# openvfo_nextion_teensy_4_0.net
KiCad netlist of a schematic drawn in EAGLE
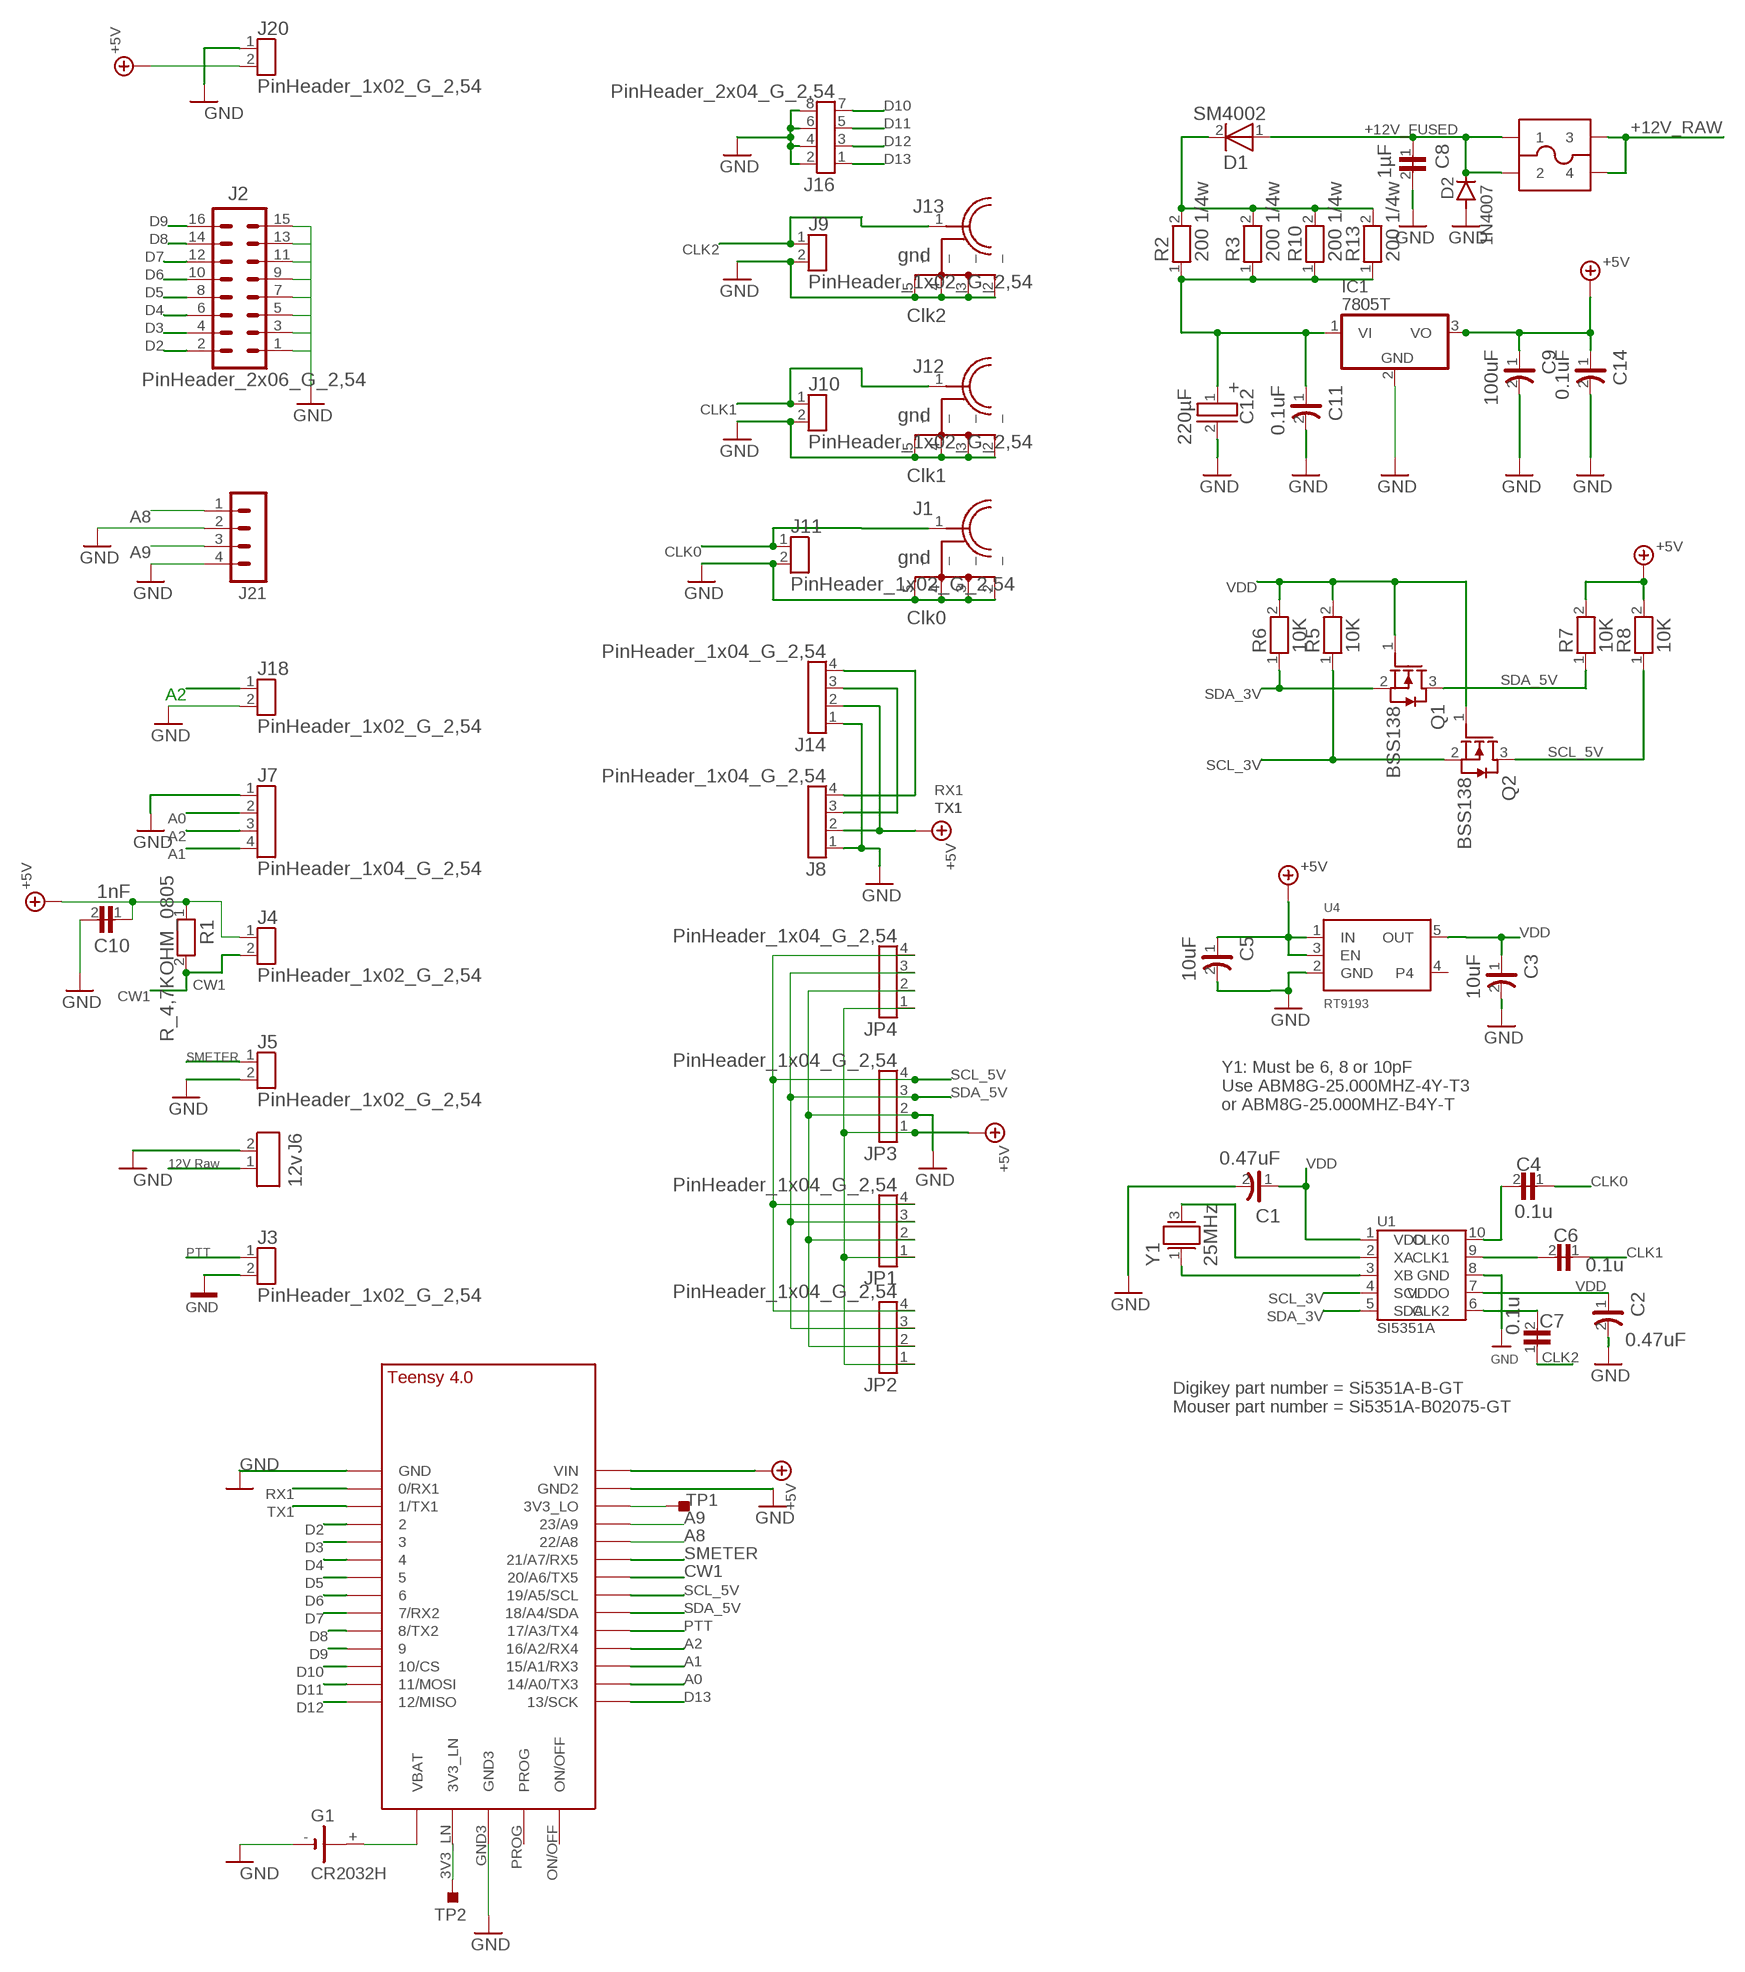
[diagram p0: schematic, sheet 1]

(export (version "E")
  (design (tool "Eeschema 10.0.6"))
  (components
    (comp (ref "C1")
      (value "0.47uF")
      (footprint "eagle-import:0805_3")
      (libsource (lib "eagle-import") (part "C-0805_3"))
    )
    (comp (ref "C2")
      (value "0.47uF")
      (footprint "eagle-import:0805_4")
      (libsource (lib "eagle-import") (part "C-0805_4"))
    )
    (comp (ref "C3")
      (value "10uF")
      (footprint "eagle-import:0805_13")
      (libsource (lib "eagle-import") (part "C-0805_13"))
    )
    (comp (ref "C4")
      (value "0.1u")
      (footprint "eagle-import:0805_81")
      (libsource (lib "eagle-import") (part "C_0805_1000PF_50V__81"))
    )
    (comp (ref "C5")
      (value "10uF")
      (footprint "eagle-import:0805_12")
      (libsource (lib "eagle-import") (part "C-0805_12"))
    )
    (comp (ref "C6")
      (value "0.1u")
      (footprint "eagle-import:0805_82")
      (libsource (lib "eagle-import") (part "C_0805_1000PF_50V__82"))
    )
    (comp (ref "C7")
      (value "0.1u")
      (footprint "eagle-import:0805_83")
      (libsource (lib "eagle-import") (part "C_0805_1000PF_50V__83"))
    )
    (comp (ref "C8")
      (value "1µF")
      (footprint "eagle-import:1206_84")
      (libsource (lib "eagle-import") (part "CMCC_1206_1,0µF_50V_10%_X7R_84"))
    )
    (comp (ref "C9")
      (value "100uF")
      (footprint "eagle-import:0805_95")
      (libsource (lib "eagle-import") (part "C-0805_95"))
    )
    (comp (ref "C10")
      (value "1nF")
      (footprint "eagle-import:0805_23")
      (libsource (lib "eagle-import") (part "C_0805_1000PF_50V__23"))
    )
    (comp (ref "C11")
      (value "0.1uF")
      (footprint "eagle-import:0805_89")
      (libsource (lib "eagle-import") (part "C-0805_89"))
    )
    (comp (ref "C12")
      (value "220µF")
      (footprint "eagle-import:D8R3,81_ELKO_104")
      (libsource (lib "eagle-import") (part "RE2J_25V_220µF_104"))
    )
    (comp (ref "C14")
      (value "0.1uF")
      (footprint "eagle-import:0805_96")
      (libsource (lib "eagle-import") (part "C-0805_96"))
    )
    (comp (ref "D1")
      (value "SM4002")
      (footprint "eagle-import:MELF_85")
      (libsource (lib "eagle-import") (part "SM4002_85"))
    )
    (comp (ref "D2")
      (value "1N4007")
      (footprint "eagle-import:DO41-10")
      (libsource (lib "eagle-import") (part "1N4004"))
    )
    (comp (ref "F1")
      (value "SMALLFUSE")
      (footprint "eagle-import:SMALLFUSE")
      (fields (field (name "MFG") "Keystone") (field (name "MPN") "3568"))
      (libsource (lib "eagle-import") (part "SMALLFUSE"))
    )
    (comp (ref "G1")
      (value "CR2032H")
      (footprint "eagle-import:CR2032H")
      (libsource (lib "eagle-import") (part "CR2032H"))
    )
    (comp (ref "IC1")
      (value "7805T")
      (footprint "eagle-import:TO220H")
      (libsource (lib "eagle-import") (part "78T05"))
    )
    (comp (ref "J1")
      (value "Clk0")
      (footprint "eagle-import:SMA-EINBAUBUCHSE_67")
      (libsource (lib "eagle-import") (part "SMA-EINBAUBUCHSE_67"))
    )
    (comp (ref "J2")
      (value "PinHeader_2x06_G_2,54")
      (footprint "eagle-import:MA08-2")
      (libsource (lib "eagle-import") (part "MA08-2"))
    )
    (comp (ref "J3")
      (value "PinHeader_1x02_G_2,54")
      (footprint "eagle-import:STIFTLEISTE_1X02_G_2,54_17")
      (libsource (lib "eagle-import") (part "PINHEADER_1X02_G_2,54_17"))
    )
    (comp (ref "J4")
      (value "PinHeader_1x02_G_2,54")
      (footprint "eagle-import:STIFTLEISTE_1X02_G_2,54_18")
      (libsource (lib "eagle-import") (part "PINHEADER_1X02_G_2,54_18"))
    )
    (comp (ref "J5")
      (value "PinHeader_1x02_G_2,54")
      (footprint "eagle-import:STIFTLEISTE_1X02_G_2,54_19")
      (libsource (lib "eagle-import") (part "PINHEADER_1X02_G_2,54_19"))
    )
    (comp (ref "J6")
      (value "12v")
      (footprint "eagle-import:SL-MTA_2.54_2POL_20")
      (libsource (lib "eagle-import") (part "640456-2_20"))
    )
    (comp (ref "J7")
      (value "PinHeader_1x04_G_2,54")
      (footprint "eagle-import:STIFTLEISTE_1X04_G_2,54_15")
      (libsource (lib "eagle-import") (part "PINHEADER_1X04_G_2,54_15"))
    )
    (comp (ref "J8")
      (value "PinHeader_1x04_G_2,54")
      (footprint "eagle-import:STIFTLEISTE_1X04_G_2,54_22")
      (libsource (lib "eagle-import") (part "PINHEADER_1X04_G_2,54_22"))
    )
    (comp (ref "J9")
      (value "PinHeader_1x02_G_2,54")
      (footprint "eagle-import:STIFTLEISTE_1X02_G_2,54_49")
      (libsource (lib "eagle-import") (part "PINHEADER_1X02_G_2,54_49"))
    )
    (comp (ref "J10")
      (value "PinHeader_1x02_G_2,54")
      (footprint "eagle-import:STIFTLEISTE_1X02_G_2,54_50")
      (libsource (lib "eagle-import") (part "PINHEADER_1X02_G_2,54_50"))
    )
    (comp (ref "J11")
      (value "PinHeader_1x02_G_2,54")
      (footprint "eagle-import:STIFTLEISTE_1X02_G_2,54_51")
      (libsource (lib "eagle-import") (part "PINHEADER_1X02_G_2,54_51"))
    )
    (comp (ref "J12")
      (value "Clk1")
      (footprint "eagle-import:SMA-EINBAUBUCHSE_68")
      (libsource (lib "eagle-import") (part "SMA-EINBAUBUCHSE_68"))
    )
    (comp (ref "J13")
      (value "Clk2")
      (footprint "eagle-import:SMA-EINBAUBUCHSE_69")
      (libsource (lib "eagle-import") (part "SMA-EINBAUBUCHSE_69"))
    )
    (comp (ref "J14")
      (value "PinHeader_1x04_G_2,54")
      (footprint "eagle-import:STIFTLEISTE_1X04_G_2,54_70")
      (libsource (lib "eagle-import") (part "PINHEADER_1X04_G_2,54_70"))
    )
    (comp (ref "J16")
      (value "PinHeader_2x04_G_2,54")
      (footprint "eagle-import:STIFTLEISTE_2X04_G_2,54_71")
      (libsource (lib "eagle-import") (part "PINHEADER_2X04_G_2,54_71"))
    )
    (comp (ref "J18")
      (value "PinHeader_1x02_G_2,54")
      (footprint "eagle-import:STIFTLEISTE_1X02_G_2,54_97")
      (libsource (lib "eagle-import") (part "PINHEADER_1X02_G_2,54_97"))
    )
    (comp (ref "J20")
      (value "PinHeader_1x02_G_2,54")
      (footprint "eagle-import:STIFTLEISTE_1X02_G_2,54_137")
      (libsource (lib "eagle-import") (part "PINHEADER_1X02_G_2,54_137"))
    )
    (comp (ref "J21")
      (value "MA04-1")
      (footprint "eagle-import:MA04-1")
      (libsource (lib "eagle-import") (part "MA04-1"))
    )
    (comp (ref "JP1")
      (value "PinHeader_1x04_G_2,54")
      (footprint "eagle-import:STIFTLEISTE_1X04_G_2,54_14")
      (libsource (lib "eagle-import") (part "PINHEADER_1X04_G_2,54_14"))
    )
    (comp (ref "JP2")
      (value "PinHeader_1x04_G_2,54")
      (footprint "eagle-import:STIFTLEISTE_1X04_G_2,54_14")
      (libsource (lib "eagle-import") (part "PINHEADER_1X04_G_2,54_14"))
    )
    (comp (ref "JP3")
      (value "PinHeader_1x04_G_2,54")
      (footprint "eagle-import:STIFTLEISTE_1X04_G_2,54_14")
      (libsource (lib "eagle-import") (part "PINHEADER_1X04_G_2,54_14"))
    )
    (comp (ref "JP4")
      (value "PinHeader_1x04_G_2,54")
      (footprint "eagle-import:STIFTLEISTE_1X04_G_2,54_14")
      (libsource (lib "eagle-import") (part "PINHEADER_1X04_G_2,54_14"))
    )
    (comp (ref "Q1")
      (value "BSS138")
      (footprint "eagle-import:SOT23_3_7")
      (libsource (lib "eagle-import") (part "BSS138_7"))
    )
    (comp (ref "Q2")
      (value "BSS138")
      (footprint "eagle-import:SOT23_3_8")
      (libsource (lib "eagle-import") (part "BSS138_8"))
    )
    (comp (ref "R1")
      (value "R_4,7KOHM_0805")
      (footprint "eagle-import:0805_21")
      (libsource (lib "eagle-import") (part "R_4,7KOHM_0805_21"))
    )
    (comp (ref "R2")
      (value "200 1/4w")
      (footprint "eagle-import:0805_142")
      (libsource (lib "eagle-import") (part "R_SMD_200-OHM_0805_142"))
    )
    (comp (ref "R3")
      (value "200 1/4w")
      (footprint "eagle-import:0805_145")
      (libsource (lib "eagle-import") (part "R_SMD_200-OHM_0805_145"))
    )
    (comp (ref "R5")
      (value "10K")
      (footprint "eagle-import:0805_5")
      (libsource (lib "eagle-import") (part "R_SMD_10K_0805_5"))
    )
    (comp (ref "R6")
      (value "10K")
      (footprint "eagle-import:0805_6")
      (libsource (lib "eagle-import") (part "R_SMD_10K_0805_6"))
    )
    (comp (ref "R7")
      (value "10K")
      (footprint "eagle-import:0805_9")
      (libsource (lib "eagle-import") (part "R_SMD_10K_0805_9"))
    )
    (comp (ref "R8")
      (value "10K")
      (footprint "eagle-import:0805_10")
      (libsource (lib "eagle-import") (part "R_SMD_10K_0805_10"))
    )
    (comp (ref "R10")
      (value "200 1/4w")
      (footprint "eagle-import:0805_146")
      (libsource (lib "eagle-import") (part "R_SMD_200-OHM_0805_146"))
    )
    (comp (ref "R13")
      (value "200 1/4w")
      (footprint "eagle-import:0805_147")
      (libsource (lib "eagle-import") (part "R_SMD_200-OHM_0805_147"))
    )
    (comp (ref "TP1")
      (value "TESTPOINT_TPS-PAD-036")
      (footprint "eagle-import:TESTPOINT_PAD-036")
      (libsource (lib "eagle-import") (part "TESTPOINT_TPS-PAD-036"))
    )
    (comp (ref "TP2")
      (value "TESTPOINT_TPS-PAD-036")
      (footprint "eagle-import:TESTPOINT_PAD-036")
      (libsource (lib "eagle-import") (part "TESTPOINT_TPS-PAD-036"))
    )
    (comp (ref "U$1")
      (value "TEENSY_4.0")
      (footprint "eagle-import:TEENSY_4.0")
      (libsource (lib "eagle-import") (part "TEENSY_4.0"))
    )
    (comp (ref "U1")
      (value "SI5351A")
      (footprint "eagle-import:MSOP10_WB3X3_P0,5_0")
      (libsource (lib "eagle-import") (part "SI5351A_0"))
    )
    (comp (ref "U4")
      (value "RT9193")
      (footprint "eagle-import:SOT23-5_11")
      (libsource (lib "eagle-import") (part "VREG_SOT23-5_11"))
    )
    (comp (ref "Y1")
      (value "25MHz")
      (footprint "eagle-import:CFPX-104_1")
      (libsource (lib "eagle-import") (part "LFXTAL033075_1"))
    )
  )
  (nets
    (net (code "1") (name "+5V") (class "Default")
      (node (ref "C10") (pin "1") (pinfunction "1_1") (pintype "passive"))
      (node (ref "C14") (pin "1") (pinfunction "1_1") (pintype "passive"))
      (node (ref "C5") (pin "1") (pinfunction "1_1") (pintype "passive"))
      (node (ref "C9") (pin "1") (pinfunction "1_1") (pintype "passive"))
      (node (ref "IC1") (pin "3") (pinfunction "VO_3") (pintype "passive"))
      (node (ref "J14") (pin "2") (pinfunction "2_2") (pintype "passive"))
      (node (ref "J20") (pin "2") (pinfunction "2_2") (pintype "passive"))
      (node (ref "J4") (pin "1") (pinfunction "1_1") (pintype "passive"))
      (node (ref "J8") (pin "2") (pinfunction "2_2") (pintype "passive"))
      (node (ref "JP1") (pin "1") (pinfunction "1_1") (pintype "passive"))
      (node (ref "JP2") (pin "1") (pinfunction "1_1") (pintype "passive"))
      (node (ref "JP3") (pin "1") (pinfunction "1_1") (pintype "passive"))
      (node (ref "JP4") (pin "1") (pinfunction "1_1") (pintype "passive"))
      (node (ref "R1") (pin "1") (pinfunction "1_1") (pintype "passive"))
      (node (ref "R7") (pin "2") (pinfunction "2_2") (pintype "passive"))
      (node (ref "R8") (pin "2") (pinfunction "2_2") (pintype "passive"))
      (node (ref "U$1") (pin "VIN") (pinfunction "VIN_VIN") (pintype "bidirectional"))
      (node (ref "U4") (pin "1") (pinfunction "IN_1") (pintype "power_in"))
      (node (ref "U4") (pin "3") (pinfunction "EN_3") (pintype "input"))
    )
    (net (code "2") (name "/+12V_FUSED") (class "Default")
      (node (ref "C8") (pin "1") (pinfunction "1_1") (pintype "passive"))
      (node (ref "D1") (pin "1") (pinfunction "1_1") (pintype "passive"))
      (node (ref "D2") (pin "C") (pinfunction "C_C") (pintype "passive"))
      (node (ref "F1") (pin "P$1") (pinfunction "1_P$1") (pintype "bidirectional"))
      (node (ref "F1") (pin "P$2") (pinfunction "2_P$2") (pintype "bidirectional"))
    )
    (net (code "3") (name "/+12V_RAW") (class "Default")
      (node (ref "F1") (pin "P$3") (pinfunction "3_P$3") (pintype "bidirectional"))
      (node (ref "F1") (pin "P$4") (pinfunction "4_P$4") (pintype "bidirectional"))
      (node (ref "J6") (pin "1") (pinfunction "1_1") (pintype "passive"))
    )
    (net (code "4") (name "/A0") (class "Default")
      (node (ref "J7") (pin "2") (pinfunction "2_2") (pintype "passive"))
      (node (ref "U$1") (pin "14/A0") (pinfunction "14/A0/TX3_14/A0") (pintype "bidirectional"))
    )
    (net (code "5") (name "/A1") (class "Default")
      (node (ref "J7") (pin "4") (pinfunction "4_4") (pintype "passive"))
      (node (ref "U$1") (pin "15/A1") (pinfunction "15/A1/RX3_15/A1") (pintype "bidirectional"))
    )
    (net (code "6") (name "/A2") (class "Default")
      (node (ref "J18") (pin "1") (pinfunction "1_1") (pintype "passive"))
      (node (ref "J7") (pin "3") (pinfunction "3_3") (pintype "passive"))
      (node (ref "U$1") (pin "16/A2") (pinfunction "16/A2/RX4_16/A2") (pintype "bidirectional"))
    )
    (net (code "7") (name "/A8") (class "Default")
      (node (ref "J21") (pin "1") (pinfunction "1_1") (pintype "passive"))
      (node (ref "U$1") (pin "22/A8") (pinfunction "22/A8_22/A8") (pintype "bidirectional"))
    )
    (net (code "8") (name "/A9") (class "Default")
      (node (ref "J21") (pin "3") (pinfunction "3_3") (pintype "passive"))
      (node (ref "U$1") (pin "23/A9") (pinfunction "23/A9_23/A9") (pintype "bidirectional"))
    )
    (net (code "9") (name "/CLK0") (class "Default")
      (node (ref "C4") (pin "1") (pinfunction "1_1") (pintype "passive"))
      (node (ref "J1") (pin "1") (pinfunction "1_1") (pintype "passive"))
      (node (ref "J11") (pin "1") (pinfunction "1_1") (pintype "passive"))
    )
    (net (code "10") (name "/CLK1") (class "Default")
      (node (ref "C6") (pin "1") (pinfunction "1_1") (pintype "passive"))
      (node (ref "J10") (pin "1") (pinfunction "1_1") (pintype "passive"))
      (node (ref "J12") (pin "1") (pinfunction "1_1") (pintype "passive"))
    )
    (net (code "11") (name "/CLK2") (class "Default")
      (node (ref "C7") (pin "1") (pinfunction "1_1") (pintype "passive"))
      (node (ref "J13") (pin "1") (pinfunction "1_1") (pintype "passive"))
      (node (ref "J9") (pin "1") (pinfunction "1_1") (pintype "passive"))
    )
    (net (code "12") (name "/CW1") (class "Default")
      (node (ref "J4") (pin "2") (pinfunction "2_2") (pintype "passive"))
      (node (ref "R1") (pin "2") (pinfunction "2_2") (pintype "passive"))
      (node (ref "U$1") (pin "20/A6") (pinfunction "20/A6/TX5_20/A6") (pintype "bidirectional"))
    )
    (net (code "13") (name "/D2") (class "Default")
      (node (ref "J2") (pin "2") (pinfunction "2_2") (pintype "passive"))
      (node (ref "U$1") (pin "2") (pinfunction "2_2") (pintype "bidirectional"))
    )
    (net (code "14") (name "/D3") (class "Default")
      (node (ref "J2") (pin "4") (pinfunction "4_4") (pintype "passive"))
      (node (ref "U$1") (pin "3/CANTX") (pinfunction "3_3/CANTX") (pintype "bidirectional"))
    )
    (net (code "15") (name "/D4") (class "Default")
      (node (ref "J2") (pin "6") (pinfunction "6_6") (pintype "passive"))
      (node (ref "U$1") (pin "4/CANRX") (pinfunction "4_4/CANRX") (pintype "bidirectional"))
    )
    (net (code "16") (name "/D5") (class "Default")
      (node (ref "J2") (pin "8") (pinfunction "8_8") (pintype "passive"))
      (node (ref "U$1") (pin "5") (pinfunction "5_5") (pintype "bidirectional"))
    )
    (net (code "17") (name "/D6") (class "Default")
      (node (ref "J2") (pin "10") (pinfunction "10_10") (pintype "passive"))
      (node (ref "U$1") (pin "6") (pinfunction "6_6") (pintype "bidirectional"))
    )
    (net (code "18") (name "/D7") (class "Default")
      (node (ref "J2") (pin "12") (pinfunction "12_12") (pintype "passive"))
      (node (ref "U$1") (pin "7") (pinfunction "7/RX2_7") (pintype "bidirectional"))
    )
    (net (code "19") (name "/D8") (class "Default")
      (node (ref "J2") (pin "14") (pinfunction "14_14") (pintype "passive"))
      (node (ref "U$1") (pin "8") (pinfunction "8/TX2_8") (pintype "bidirectional"))
    )
    (net (code "20") (name "/D9") (class "Default")
      (node (ref "J2") (pin "16") (pinfunction "16_16") (pintype "passive"))
      (node (ref "U$1") (pin "9/CS") (pinfunction "9_9/CS") (pintype "bidirectional"))
    )
    (net (code "21") (name "/D10") (class "Default")
      (node (ref "J16") (pin "7") (pinfunction "7_7") (pintype "passive"))
      (node (ref "U$1") (pin "10/CS") (pinfunction "10/CS_10/CS") (pintype "bidirectional"))
    )
    (net (code "22") (name "/D11") (class "Default")
      (node (ref "J16") (pin "5") (pinfunction "5_5") (pintype "passive"))
      (node (ref "U$1") (pin "11/MOSI") (pinfunction "11/MOSI_11/MOSI") (pintype "bidirectional"))
    )
    (net (code "23") (name "/D12") (class "Default")
      (node (ref "J16") (pin "3") (pinfunction "3_3") (pintype "passive"))
      (node (ref "U$1") (pin "12/MISO") (pinfunction "12/MISO_12/MISO") (pintype "bidirectional"))
    )
    (net (code "24") (name "/D13") (class "Default")
      (node (ref "J16") (pin "1") (pinfunction "1_1") (pintype "passive"))
      (node (ref "U$1") (pin "13/SCK") (pinfunction "13/SCK_13/SCK") (pintype "bidirectional"))
    )
    (net (code "25") (name "/PTT") (class "Default")
      (node (ref "J3") (pin "1") (pinfunction "1_1") (pintype "passive"))
      (node (ref "U$1") (pin "17/A3") (pinfunction "17/A3/TX4_17/A3") (pintype "bidirectional"))
    )
    (net (code "26") (name "/RX1") (class "Default")
      (node (ref "J14") (pin "4") (pinfunction "4_4") (pintype "passive"))
      (node (ref "J8") (pin "4") (pinfunction "4_4") (pintype "passive"))
      (node (ref "U$1") (pin "0/RX") (pinfunction "0/RX1_0/RX") (pintype "bidirectional"))
    )
    (net (code "27") (name "/SCL_3V") (class "Default")
      (node (ref "Q2") (pin "2") (pinfunction "2_2") (pintype "passive"))
      (node (ref "R5") (pin "1") (pinfunction "1_1") (pintype "passive"))
      (node (ref "U1") (pin "4") (pinfunction "SCL_4") (pintype "passive"))
    )
    (net (code "28") (name "/SCL_5V") (class "Default")
      (node (ref "JP1") (pin "4") (pinfunction "4_4") (pintype "passive"))
      (node (ref "JP2") (pin "4") (pinfunction "4_4") (pintype "passive"))
      (node (ref "JP3") (pin "4") (pinfunction "4_4") (pintype "passive"))
      (node (ref "JP4") (pin "4") (pinfunction "4_4") (pintype "passive"))
      (node (ref "Q2") (pin "3") (pinfunction "3_3") (pintype "passive"))
      (node (ref "R8") (pin "1") (pinfunction "1_1") (pintype "passive"))
      (node (ref "U$1") (pin "19/A5/SCL") (pinfunction "19/A5/SCL_19/A5/SCL") (pintype "bidirectional"))
    )
    (net (code "29") (name "/SDA_3V") (class "Default")
      (node (ref "Q1") (pin "2") (pinfunction "2_2") (pintype "passive"))
      (node (ref "R6") (pin "1") (pinfunction "1_1") (pintype "passive"))
      (node (ref "U1") (pin "5") (pinfunction "SDA_5") (pintype "passive"))
    )
    (net (code "30") (name "/SDA_5V") (class "Default")
      (node (ref "JP1") (pin "3") (pinfunction "3_3") (pintype "passive"))
      (node (ref "JP2") (pin "3") (pinfunction "3_3") (pintype "passive"))
      (node (ref "JP3") (pin "3") (pinfunction "3_3") (pintype "passive"))
      (node (ref "JP4") (pin "3") (pinfunction "3_3") (pintype "passive"))
      (node (ref "Q1") (pin "3") (pinfunction "3_3") (pintype "passive"))
      (node (ref "R7") (pin "1") (pinfunction "1_1") (pintype "passive"))
      (node (ref "U$1") (pin "18/A4/SDA") (pinfunction "18/A4/SDA_18/A4/SDA") (pintype "bidirectional"))
    )
    (net (code "31") (name "/SMETER") (class "Default")
      (node (ref "J5") (pin "1") (pinfunction "1_1") (pintype "passive"))
      (node (ref "U$1") (pin "21/A7") (pinfunction "21/A7/RX5_21/A7") (pintype "bidirectional"))
    )
    (net (code "32") (name "/TX1") (class "Default")
      (node (ref "J14") (pin "3") (pinfunction "3_3") (pintype "passive"))
      (node (ref "J8") (pin "3") (pinfunction "3_3") (pintype "passive"))
      (node (ref "U$1") (pin "1/TX") (pinfunction "1/TX1_1/TX") (pintype "bidirectional"))
    )
    (net (code "33") (name "/VDD") (class "Default")
      (node (ref "C1") (pin "1") (pinfunction "1_1") (pintype "passive"))
      (node (ref "C2") (pin "1") (pinfunction "1_1") (pintype "passive"))
      (node (ref "C3") (pin "1") (pinfunction "1_1") (pintype "passive"))
      (node (ref "Q1") (pin "1") (pinfunction "1_1") (pintype "passive"))
      (node (ref "Q2") (pin "1") (pinfunction "1_1") (pintype "passive"))
      (node (ref "R5") (pin "2") (pinfunction "2_2") (pintype "passive"))
      (node (ref "R6") (pin "2") (pinfunction "2_2") (pintype "passive"))
      (node (ref "U1") (pin "1") (pinfunction "VDD_1") (pintype "passive"))
      (node (ref "U1") (pin "7") (pinfunction "VDDO_7") (pintype "passive"))
      (node (ref "U4") (pin "5") (pinfunction "OUT_5") (pintype "power_in"))
    )
    (net (code "34") (name "GND") (class "Default")
      (node (ref "C1") (pin "2") (pinfunction "2_2") (pintype "passive"))
      (node (ref "C10") (pin "2") (pinfunction "2_2") (pintype "passive"))
      (node (ref "C11") (pin "2") (pinfunction "2_2") (pintype "passive"))
      (node (ref "C12") (pin "2") (pinfunction "2_2") (pintype "passive"))
      (node (ref "C14") (pin "2") (pinfunction "2_2") (pintype "passive"))
      (node (ref "C2") (pin "2") (pinfunction "2_2") (pintype "passive"))
      (node (ref "C3") (pin "2") (pinfunction "2_2") (pintype "passive"))
      (node (ref "C5") (pin "2") (pinfunction "2_2") (pintype "passive"))
      (node (ref "C8") (pin "2") (pinfunction "2_2") (pintype "passive"))
      (node (ref "C9") (pin "2") (pinfunction "2_2") (pintype "passive"))
      (node (ref "D2") (pin "A") (pinfunction "A_A") (pintype "passive"))
      (node (ref "G1") (pin "-") (pinfunction "-_-") (pintype "passive"))
      (node (ref "IC1") (pin "2") (pinfunction "GND_2") (pintype "passive"))
      (node (ref "J1") (pin "2") (pinfunction "__2") (pintype "passive"))
      (node (ref "J1") (pin "3") (pinfunction "__3") (pintype "passive"))
      (node (ref "J1") (pin "4") (pinfunction "__4") (pintype "passive"))
      (node (ref "J1") (pin "5") (pinfunction "__5") (pintype "passive"))
      (node (ref "J10") (pin "2") (pinfunction "2_2") (pintype "passive"))
      (node (ref "J11") (pin "2") (pinfunction "2_2") (pintype "passive"))
      (node (ref "J12") (pin "2") (pinfunction "__2") (pintype "passive"))
      (node (ref "J12") (pin "3") (pinfunction "__3") (pintype "passive"))
      (node (ref "J12") (pin "4") (pinfunction "__4") (pintype "passive"))
      (node (ref "J12") (pin "5") (pinfunction "__5") (pintype "passive"))
      (node (ref "J13") (pin "2") (pinfunction "__2") (pintype "passive"))
      (node (ref "J13") (pin "3") (pinfunction "__3") (pintype "passive"))
      (node (ref "J13") (pin "4") (pinfunction "__4") (pintype "passive"))
      (node (ref "J13") (pin "5") (pinfunction "__5") (pintype "passive"))
      (node (ref "J14") (pin "1") (pinfunction "1_1") (pintype "passive"))
      (node (ref "J16") (pin "2") (pinfunction "2_2") (pintype "passive"))
      (node (ref "J16") (pin "4") (pinfunction "4_4") (pintype "passive"))
      (node (ref "J16") (pin "6") (pinfunction "6_6") (pintype "passive"))
      (node (ref "J16") (pin "8") (pinfunction "8_8") (pintype "passive"))
      (node (ref "J18") (pin "2") (pinfunction "2_2") (pintype "passive"))
      (node (ref "J2") (pin "1") (pinfunction "1_1") (pintype "passive"))
      (node (ref "J2") (pin "11") (pinfunction "11_11") (pintype "passive"))
      (node (ref "J2") (pin "13") (pinfunction "13_13") (pintype "passive"))
      (node (ref "J2") (pin "15") (pinfunction "15_15") (pintype "passive"))
      (node (ref "J2") (pin "3") (pinfunction "3_3") (pintype "passive"))
      (node (ref "J2") (pin "5") (pinfunction "5_5") (pintype "passive"))
      (node (ref "J2") (pin "7") (pinfunction "7_7") (pintype "passive"))
      (node (ref "J2") (pin "9") (pinfunction "9_9") (pintype "passive"))
      (node (ref "J20") (pin "1") (pinfunction "1_1") (pintype "passive"))
      (node (ref "J21") (pin "2") (pinfunction "2_2") (pintype "passive"))
      (node (ref "J21") (pin "4") (pinfunction "4_4") (pintype "passive"))
      (node (ref "J3") (pin "2") (pinfunction "2_2") (pintype "passive"))
      (node (ref "J5") (pin "2") (pinfunction "2_2") (pintype "passive"))
      (node (ref "J6") (pin "2") (pinfunction "2_2") (pintype "passive"))
      (node (ref "J7") (pin "1") (pinfunction "1_1") (pintype "passive"))
      (node (ref "J8") (pin "1") (pinfunction "1_1") (pintype "passive"))
      (node (ref "J9") (pin "2") (pinfunction "2_2") (pintype "passive"))
      (node (ref "JP1") (pin "2") (pinfunction "2_2") (pintype "passive"))
      (node (ref "JP2") (pin "2") (pinfunction "2_2") (pintype "passive"))
      (node (ref "JP3") (pin "2") (pinfunction "2_2") (pintype "passive"))
      (node (ref "JP4") (pin "2") (pinfunction "2_2") (pintype "passive"))
      (node (ref "U$1") (pin "GND") (pinfunction "GND_GND") (pintype "bidirectional"))
      (node (ref "U$1") (pin "GND2") (pinfunction "GND2_GND2") (pintype "bidirectional"))
      (node (ref "U$1") (pin "GND3") (pinfunction "GND3_GND3") (pintype "bidirectional"))
      (node (ref "U1") (pin "8") (pinfunction "GND_8") (pintype "passive"))
      (node (ref "U4") (pin "2") (pinfunction "GND_2") (pintype "power_in"))
    )
    (net (code "35") (name "Net-(D1-Pad2)") (class "Default")
      (node (ref "D1") (pin "2") (pinfunction "2_2") (pintype "passive"))
      (node (ref "R10") (pin "2") (pinfunction "2_2") (pintype "passive"))
      (node (ref "R13") (pin "2") (pinfunction "2_2") (pintype "passive"))
      (node (ref "R2") (pin "2") (pinfunction "2_2") (pintype "passive"))
      (node (ref "R3") (pin "2") (pinfunction "2_2") (pintype "passive"))
    )
    (net (code "36") (name "Net-(IC1-VI)") (class "Default")
      (node (ref "C11") (pin "1") (pinfunction "1_1") (pintype "passive"))
      (node (ref "C12") (pin "1") (pinfunction "1_1") (pintype "passive"))
      (node (ref "IC1") (pin "1") (pinfunction "VI_1") (pintype "input"))
      (node (ref "R10") (pin "1") (pinfunction "1_1") (pintype "passive"))
      (node (ref "R13") (pin "1") (pinfunction "1_1") (pintype "passive"))
      (node (ref "R2") (pin "1") (pinfunction "1_1") (pintype "passive"))
      (node (ref "R3") (pin "1") (pinfunction "1_1") (pintype "passive"))
    )
    (net (code "37") (name "Net-(TP1-TP)") (class "Default")
      (node (ref "TP1") (pin "1") (pinfunction "TP_1") (pintype "passive"))
      (node (ref "U$1") (pin "3V3_LO") (pinfunction "3V3_LO_3V3_LO") (pintype "bidirectional"))
    )
    (net (code "38") (name "Net-(TP2-TP)") (class "Default")
      (node (ref "TP2") (pin "1") (pinfunction "TP_1") (pintype "passive"))
      (node (ref "U$1") (pin "3V3_LN") (pinfunction "3V3_LN_3V3_LN") (pintype "bidirectional"))
    )
    (net (code "39") (name "Net-(U$1-VBAT)") (class "Default")
      (node (ref "G1") (pin "+") (pinfunction "+_+") (pintype "passive"))
      (node (ref "U$1") (pin "VBAT\\") (pinfunction "VBAT_VBAT\\") (pintype "bidirectional"))
    )
    (net (code "40") (name "Net-(U1-CLK0)") (class "Default")
      (node (ref "C4") (pin "2") (pinfunction "2_2") (pintype "passive"))
      (node (ref "U1") (pin "10") (pinfunction "CLK0_10") (pintype "passive"))
    )
    (net (code "41") (name "Net-(U1-CLK1)") (class "Default")
      (node (ref "C6") (pin "2") (pinfunction "2_2") (pintype "passive"))
      (node (ref "U1") (pin "9") (pinfunction "CLK1_9") (pintype "passive"))
    )
    (net (code "42") (name "Net-(U1-CLK2)") (class "Default")
      (node (ref "C7") (pin "2") (pinfunction "2_2") (pintype "passive"))
      (node (ref "U1") (pin "6") (pinfunction "CLK2_6") (pintype "passive"))
    )
    (net (code "43") (name "Net-(U1-XA)") (class "Default")
      (node (ref "U1") (pin "2") (pinfunction "XA_2") (pintype "passive"))
      (node (ref "Y1") (pin "3") (pinfunction "3_3") (pintype "passive"))
    )
    (net (code "44") (name "Net-(U1-XB)") (class "Default")
      (node (ref "U1") (pin "3") (pinfunction "XB_3") (pintype "passive"))
      (node (ref "Y1") (pin "1") (pinfunction "1_1") (pintype "passive"))
    )
    (net (code "45") (name "unconnected-(G1-+-Pad+@1)") (class "Default")
      (node (ref "G1") (pin "+@1") (pinfunction "+_+@1") (pintype "passive"))
    )
    (net (code "46") (name "unconnected-(U$1-PadON{slash}OFF)") (class "Default")
      (node (ref "U$1") (pin "ON/OFF") (pinfunction "ON/OFF_ON/OFF") (pintype "bidirectional"))
    )
    (net (code "47") (name "unconnected-(U$1-PadPROG)") (class "Default")
      (node (ref "U$1") (pin "PROG") (pinfunction "PROG_PROG") (pintype "bidirectional"))
    )
    (net (code "48") (name "unconnected-(U4-P4-Pad4)") (class "Default")
      (node (ref "U4") (pin "4") (pinfunction "P4_4") (pintype "bidirectional"))
    )
  )
)
